# ev_emulator.net
KiCad netlist of a schematic drawn in EAGLE
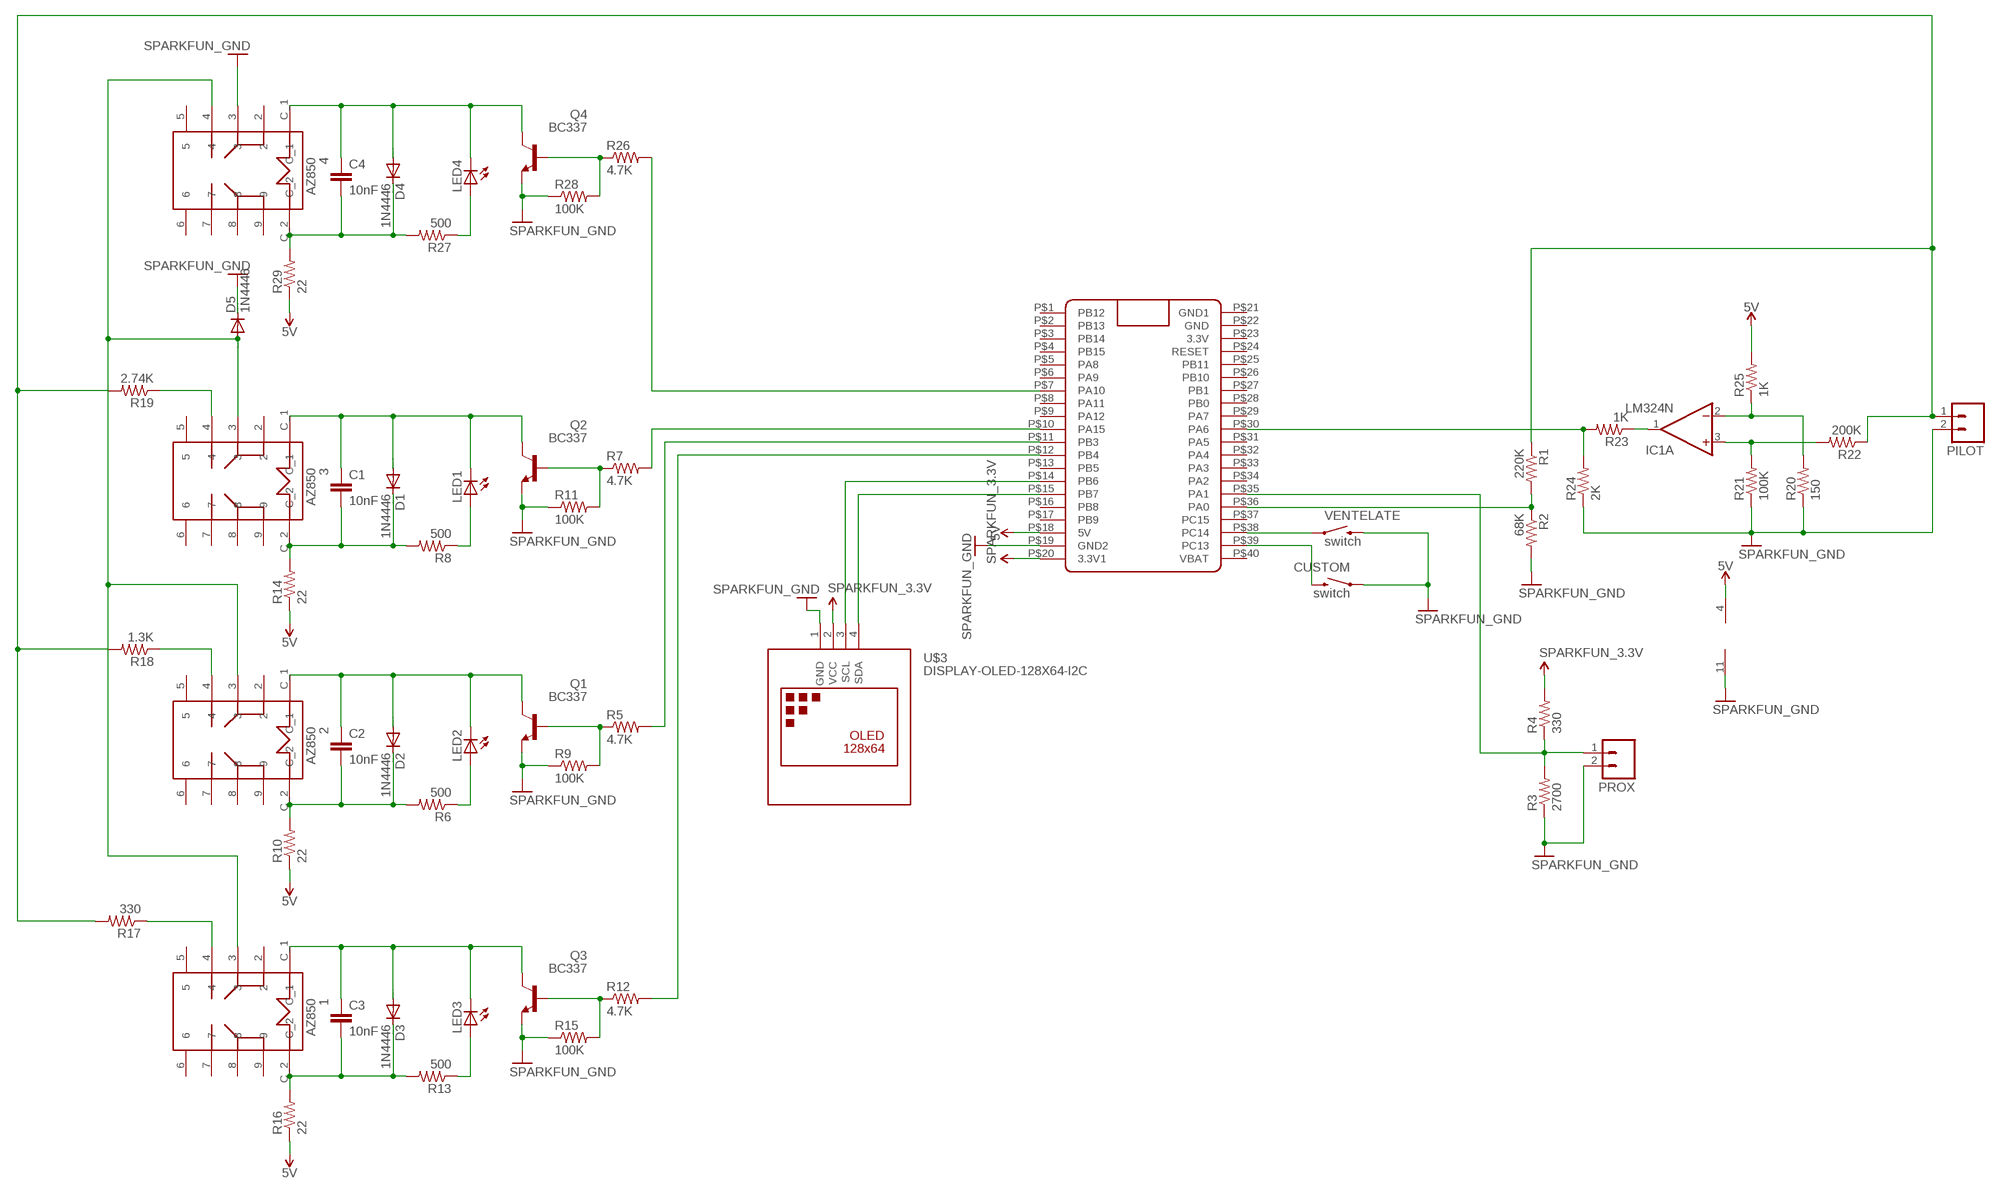
[diagram p0: schematic, sheet 1]

(export (version "E")
  (design (tool "Eeschema 10.0.6"))
  (components
    (comp (ref "1")
      (value "AZ850")
      (footprint "eagle-import:AZ850")
      (libsource (lib "eagle-import") (part "AZ850"))
    )
    (comp (ref "2")
      (value "AZ850")
      (footprint "eagle-import:AZ850")
      (libsource (lib "eagle-import") (part "AZ850"))
    )
    (comp (ref "3")
      (value "AZ850")
      (footprint "eagle-import:AZ850")
      (libsource (lib "eagle-import") (part "AZ850"))
    )
    (comp (ref "4")
      (value "AZ850")
      (footprint "eagle-import:AZ850")
      (libsource (lib "eagle-import") (part "AZ850"))
    )
    (comp (ref "C1")
      (value "10nF")
      (footprint "eagle-import:C2.5-3")
      (libsource (lib "eagle-import") (part "C2,5-3"))
    )
    (comp (ref "C2")
      (value "10nF")
      (footprint "eagle-import:C2.5-3")
      (libsource (lib "eagle-import") (part "C2,5-3"))
    )
    (comp (ref "C3")
      (value "10nF")
      (footprint "eagle-import:C2.5-3")
      (libsource (lib "eagle-import") (part "C2,5-3"))
    )
    (comp (ref "C4")
      (value "10nF")
      (footprint "eagle-import:C2.5-3")
      (libsource (lib "eagle-import") (part "C2,5-3"))
    )
    (comp (ref "CUSTOM")
      (value "switch")
      (footprint "eagle-import:SPARKFUN-ELECTROMECHANICAL_TACTILE-PTH")
      (libsource (lib "eagle-import") (part "SPARKFUN-ELECTROMECHANICAL_SWITCH-MOMENTARY-2PTH"))
    )
    (comp (ref "D1")
      (value "1N4446")
      (footprint "eagle-import:DO35-10")
      (libsource (lib "eagle-import") (part "1N4446"))
    )
    (comp (ref "D2")
      (value "1N4446")
      (footprint "eagle-import:DO35-10")
      (libsource (lib "eagle-import") (part "1N4446"))
    )
    (comp (ref "D3")
      (value "1N4446")
      (footprint "eagle-import:DO35-10")
      (libsource (lib "eagle-import") (part "1N4446"))
    )
    (comp (ref "D4")
      (value "1N4446")
      (footprint "eagle-import:DO35-10")
      (libsource (lib "eagle-import") (part "1N4446"))
    )
    (comp (ref "D5")
      (value "1N4446")
      (footprint "eagle-import:DO35-10")
      (libsource (lib "eagle-import") (part "1N4446"))
    )
    (comp (ref "IC1")
      (value "LM324N")
      (footprint "eagle-import:DIL14")
      (libsource (lib "eagle-import") (part "LM324N"))
    )
    (comp (ref "LED1")
      (value "SPARKFUN_LED-3MM-NO_SILK")
      (footprint "eagle-import:SPARKFUN_LED3MM-NS")
      (libsource (lib "eagle-import") (part "SPARKFUN_LED-3MM-NO_SILK"))
    )
    (comp (ref "LED2")
      (value "SPARKFUN_LED-3MM-NO_SILK")
      (footprint "eagle-import:SPARKFUN_LED3MM-NS")
      (libsource (lib "eagle-import") (part "SPARKFUN_LED-3MM-NO_SILK"))
    )
    (comp (ref "LED3")
      (value "SPARKFUN_LED-3MM-NO_SILK")
      (footprint "eagle-import:SPARKFUN_LED3MM-NS")
      (libsource (lib "eagle-import") (part "SPARKFUN_LED-3MM-NO_SILK"))
    )
    (comp (ref "LED4")
      (value "SPARKFUN_LED-3MM-NO_SILK")
      (footprint "eagle-import:SPARKFUN_LED3MM-NS")
      (libsource (lib "eagle-import") (part "SPARKFUN_LED-3MM-NO_SILK"))
    )
    (comp (ref "PILOT")
      (value "SPARKFUN_M02POLAR")
      (footprint "eagle-import:SPARKFUN_MOLEX-1X2")
      (libsource (lib "eagle-import") (part "SPARKFUN_M02POLAR"))
    )
    (comp (ref "PROX")
      (value "SPARKFUN_M02POLAR")
      (footprint "eagle-import:SPARKFUN_MOLEX-1X2")
      (libsource (lib "eagle-import") (part "SPARKFUN_M02POLAR"))
    )
    (comp (ref "Q1")
      (value "BC337")
      (footprint "eagle-import:TO92")
      (libsource (lib "eagle-import") (part "BC337"))
    )
    (comp (ref "Q2")
      (value "BC337")
      (footprint "eagle-import:TO92")
      (libsource (lib "eagle-import") (part "BC337"))
    )
    (comp (ref "Q3")
      (value "BC337")
      (footprint "eagle-import:TO92")
      (libsource (lib "eagle-import") (part "BC337"))
    )
    (comp (ref "Q4")
      (value "BC337")
      (footprint "eagle-import:TO92")
      (libsource (lib "eagle-import") (part "BC337"))
    )
    (comp (ref "R1")
      (value "220K")
      (footprint "eagle-import:SPARKFUN_AXIAL-0.3")
      (libsource (lib "eagle-import") (part "SPARKFUN_RESISTORAXIAL-0.3"))
    )
    (comp (ref "R2")
      (value "68K")
      (footprint "eagle-import:SPARKFUN_AXIAL-0.3")
      (libsource (lib "eagle-import") (part "SPARKFUN_RESISTORAXIAL-0.3"))
    )
    (comp (ref "R3")
      (value "2700")
      (footprint "eagle-import:SPARKFUN_AXIAL-0.3")
      (libsource (lib "eagle-import") (part "SPARKFUN_RESISTORAXIAL-0.3"))
    )
    (comp (ref "R4")
      (value "330")
      (footprint "eagle-import:SPARKFUN_AXIAL-0.3")
      (libsource (lib "eagle-import") (part "SPARKFUN_RESISTORAXIAL-0.3"))
    )
    (comp (ref "R5")
      (value "4.7K")
      (footprint "eagle-import:SPARKFUN_AXIAL-0.3")
      (libsource (lib "eagle-import") (part "SPARKFUN_RESISTORAXIAL-0.3"))
    )
    (comp (ref "R6")
      (value "500")
      (footprint "eagle-import:SPARKFUN_AXIAL-0.3")
      (libsource (lib "eagle-import") (part "SPARKFUN_RESISTORAXIAL-0.3"))
    )
    (comp (ref "R7")
      (value "4.7K")
      (footprint "eagle-import:SPARKFUN_AXIAL-0.3")
      (libsource (lib "eagle-import") (part "SPARKFUN_RESISTORAXIAL-0.3"))
    )
    (comp (ref "R8")
      (value "500")
      (footprint "eagle-import:SPARKFUN_AXIAL-0.3")
      (libsource (lib "eagle-import") (part "SPARKFUN_RESISTORAXIAL-0.3"))
    )
    (comp (ref "R9")
      (value "100K")
      (footprint "eagle-import:SPARKFUN_AXIAL-0.3")
      (libsource (lib "eagle-import") (part "SPARKFUN_RESISTORAXIAL-0.3"))
    )
    (comp (ref "R10")
      (value "22")
      (footprint "eagle-import:SPARKFUN_AXIAL-0.3")
      (libsource (lib "eagle-import") (part "SPARKFUN_RESISTORAXIAL-0.3"))
    )
    (comp (ref "R11")
      (value "100K")
      (footprint "eagle-import:SPARKFUN_AXIAL-0.3")
      (libsource (lib "eagle-import") (part "SPARKFUN_RESISTORAXIAL-0.3"))
    )
    (comp (ref "R12")
      (value "4.7K")
      (footprint "eagle-import:SPARKFUN_AXIAL-0.3")
      (libsource (lib "eagle-import") (part "SPARKFUN_RESISTORAXIAL-0.3"))
    )
    (comp (ref "R13")
      (value "500")
      (footprint "eagle-import:SPARKFUN_AXIAL-0.3")
      (libsource (lib "eagle-import") (part "SPARKFUN_RESISTORAXIAL-0.3"))
    )
    (comp (ref "R14")
      (value "22")
      (footprint "eagle-import:SPARKFUN_AXIAL-0.3")
      (libsource (lib "eagle-import") (part "SPARKFUN_RESISTORAXIAL-0.3"))
    )
    (comp (ref "R15")
      (value "100K")
      (footprint "eagle-import:SPARKFUN_AXIAL-0.3")
      (libsource (lib "eagle-import") (part "SPARKFUN_RESISTORAXIAL-0.3"))
    )
    (comp (ref "R16")
      (value "22")
      (footprint "eagle-import:SPARKFUN_AXIAL-0.3")
      (libsource (lib "eagle-import") (part "SPARKFUN_RESISTORAXIAL-0.3"))
    )
    (comp (ref "R17")
      (value "330")
      (footprint "eagle-import:SPARKFUN_AXIAL-0.3")
      (libsource (lib "eagle-import") (part "SPARKFUN_RESISTORAXIAL-0.3"))
    )
    (comp (ref "R18")
      (value "1.3K")
      (footprint "eagle-import:SPARKFUN_AXIAL-0.3")
      (libsource (lib "eagle-import") (part "SPARKFUN_RESISTORAXIAL-0.3"))
    )
    (comp (ref "R19")
      (value "2.74K")
      (footprint "eagle-import:SPARKFUN_AXIAL-0.3")
      (libsource (lib "eagle-import") (part "SPARKFUN_RESISTORAXIAL-0.3"))
    )
    (comp (ref "R20")
      (value "150")
      (footprint "eagle-import:SPARKFUN_AXIAL-0.3")
      (libsource (lib "eagle-import") (part "SPARKFUN_RESISTORAXIAL-0.3"))
    )
    (comp (ref "R21")
      (value "100K")
      (footprint "eagle-import:SPARKFUN_AXIAL-0.3")
      (libsource (lib "eagle-import") (part "SPARKFUN_RESISTORAXIAL-0.3"))
    )
    (comp (ref "R22")
      (value "200K")
      (footprint "eagle-import:SPARKFUN_AXIAL-0.3")
      (libsource (lib "eagle-import") (part "SPARKFUN_RESISTORAXIAL-0.3"))
    )
    (comp (ref "R23")
      (value "1K")
      (footprint "eagle-import:SPARKFUN_AXIAL-0.3")
      (libsource (lib "eagle-import") (part "SPARKFUN_RESISTORAXIAL-0.3"))
    )
    (comp (ref "R24")
      (value "2K")
      (footprint "eagle-import:SPARKFUN_AXIAL-0.3")
      (libsource (lib "eagle-import") (part "SPARKFUN_RESISTORAXIAL-0.3"))
    )
    (comp (ref "R25")
      (value "1K")
      (footprint "eagle-import:SPARKFUN_AXIAL-0.3")
      (libsource (lib "eagle-import") (part "SPARKFUN_RESISTORAXIAL-0.3"))
    )
    (comp (ref "R26")
      (value "4.7K")
      (footprint "eagle-import:SPARKFUN_AXIAL-0.3")
      (libsource (lib "eagle-import") (part "SPARKFUN_RESISTORAXIAL-0.3"))
    )
    (comp (ref "R27")
      (value "500")
      (footprint "eagle-import:SPARKFUN_AXIAL-0.3")
      (libsource (lib "eagle-import") (part "SPARKFUN_RESISTORAXIAL-0.3"))
    )
    (comp (ref "R28")
      (value "100K")
      (footprint "eagle-import:SPARKFUN_AXIAL-0.3")
      (libsource (lib "eagle-import") (part "SPARKFUN_RESISTORAXIAL-0.3"))
    )
    (comp (ref "R29")
      (value "22")
      (footprint "eagle-import:SPARKFUN_AXIAL-0.3")
      (libsource (lib "eagle-import") (part "SPARKFUN_RESISTORAXIAL-0.3"))
    )
    (comp (ref "U$1")
      (value "BLUE_PILL")
      (footprint "eagle-import:BLUE_PILL")
      (libsource (lib "eagle-import") (part "BLUE_PILL"))
    )
    (comp (ref "U$3")
      (value "DISPLAY-OLED-128X64-I2C")
      (footprint "eagle-import:DISPLAY-OLED-128X64-I2C")
      (libsource (lib "eagle-import") (part "DISPLAY-OLED-128X64-I2C"))
    )
    (comp (ref "VENTELATE")
      (value "switch")
      (footprint "eagle-import:SPARKFUN-ELECTROMECHANICAL_TACTILE-PTH")
      (libsource (lib "eagle-import") (part "SPARKFUN-ELECTROMECHANICAL_SWITCH-MOMENTARY-2PTH"))
    )
  )
  (nets
    (net (code "1") (name "/GND1") (class "Default")
      (node (ref "U$1") (pin "P$21") (pinfunction "GND1_P$21") (pintype "power_in"))
    )
    (net (code "2") (name "5V") (class "Default")
      (node (ref "IC1") (pin "4") (pinfunction "V+_4") (pintype "power_in"))
      (node (ref "R10") (pin "P$1") (pinfunction "1_P$1") (pintype "passive"))
      (node (ref "R14") (pin "P$1") (pinfunction "1_P$1") (pintype "passive"))
      (node (ref "R16") (pin "P$1") (pinfunction "1_P$1") (pintype "passive"))
      (node (ref "R25") (pin "P$2") (pinfunction "2_P$2") (pintype "passive"))
      (node (ref "R29") (pin "P$1") (pinfunction "1_P$1") (pintype "passive"))
      (node (ref "U$1") (pin "P$18") (pinfunction "5V_P$18") (pintype "bidirectional"))
    )
    (net (code "3") (name "Net-(1-Pad3)") (class "Default")
      (node (ref "1") (pin "3") (pinfunction "3_3") (pintype "bidirectional"))
      (node (ref "2") (pin "3") (pinfunction "3_3") (pintype "bidirectional"))
      (node (ref "3") (pin "3") (pinfunction "3_3") (pintype "bidirectional"))
      (node (ref "4") (pin "4") (pinfunction "4_4") (pintype "bidirectional"))
      (node (ref "D5") (pin "A") (pinfunction "A_A") (pintype "passive"))
    )
    (net (code "4") (name "Net-(1-С_1)") (class "Default")
      (node (ref "1") (pin "C_1") (pinfunction "С_1_C_1") (pintype "power_in"))
      (node (ref "C3") (pin "1") (pinfunction "1_1") (pintype "passive"))
      (node (ref "D3") (pin "A") (pinfunction "A_A") (pintype "passive"))
      (node (ref "LED3") (pin "K") (pinfunction "C_K") (pintype "passive"))
      (node (ref "Q3") (pin "3") (pinfunction "C_3") (pintype "passive"))
    )
    (net (code "5") (name "Net-(1-С_2)") (class "Default")
      (node (ref "1") (pin "C_2") (pinfunction "С_2_C_2") (pintype "power_in"))
      (node (ref "C3") (pin "2") (pinfunction "2_2") (pintype "passive"))
      (node (ref "D3") (pin "C") (pinfunction "C_C") (pintype "passive"))
      (node (ref "R13") (pin "P$2") (pinfunction "2_P$2") (pintype "passive"))
      (node (ref "R16") (pin "P$2") (pinfunction "2_P$2") (pintype "passive"))
    )
    (net (code "6") (name "Net-(2-С_1)") (class "Default")
      (node (ref "2") (pin "C_1") (pinfunction "С_1_C_1") (pintype "power_in"))
      (node (ref "C2") (pin "1") (pinfunction "1_1") (pintype "passive"))
      (node (ref "D2") (pin "A") (pinfunction "A_A") (pintype "passive"))
      (node (ref "LED2") (pin "K") (pinfunction "C_K") (pintype "passive"))
      (node (ref "Q1") (pin "3") (pinfunction "C_3") (pintype "passive"))
    )
    (net (code "7") (name "Net-(2-С_2)") (class "Default")
      (node (ref "2") (pin "C_2") (pinfunction "С_2_C_2") (pintype "power_in"))
      (node (ref "C2") (pin "2") (pinfunction "2_2") (pintype "passive"))
      (node (ref "D2") (pin "C") (pinfunction "C_C") (pintype "passive"))
      (node (ref "R10") (pin "P$2") (pinfunction "2_P$2") (pintype "passive"))
      (node (ref "R6") (pin "P$2") (pinfunction "2_P$2") (pintype "passive"))
    )
    (net (code "8") (name "Net-(3-С_1)") (class "Default")
      (node (ref "3") (pin "C_1") (pinfunction "С_1_C_1") (pintype "power_in"))
      (node (ref "C1") (pin "1") (pinfunction "1_1") (pintype "passive"))
      (node (ref "D1") (pin "A") (pinfunction "A_A") (pintype "passive"))
      (node (ref "LED1") (pin "K") (pinfunction "C_K") (pintype "passive"))
      (node (ref "Q2") (pin "3") (pinfunction "C_3") (pintype "passive"))
    )
    (net (code "9") (name "Net-(3-С_2)") (class "Default")
      (node (ref "3") (pin "C_2") (pinfunction "С_2_C_2") (pintype "power_in"))
      (node (ref "C1") (pin "2") (pinfunction "2_2") (pintype "passive"))
      (node (ref "D1") (pin "C") (pinfunction "C_C") (pintype "passive"))
      (node (ref "R14") (pin "P$2") (pinfunction "2_P$2") (pintype "passive"))
      (node (ref "R8") (pin "P$2") (pinfunction "2_P$2") (pintype "passive"))
    )
    (net (code "10") (name "Net-(4-С_1)") (class "Default")
      (node (ref "4") (pin "C_1") (pinfunction "С_1_C_1") (pintype "power_in"))
      (node (ref "C4") (pin "1") (pinfunction "1_1") (pintype "passive"))
      (node (ref "D4") (pin "A") (pinfunction "A_A") (pintype "passive"))
      (node (ref "LED4") (pin "K") (pinfunction "C_K") (pintype "passive"))
      (node (ref "Q4") (pin "3") (pinfunction "C_3") (pintype "passive"))
    )
    (net (code "11") (name "Net-(4-С_2)") (class "Default")
      (node (ref "4") (pin "C_2") (pinfunction "С_2_C_2") (pintype "power_in"))
      (node (ref "C4") (pin "2") (pinfunction "2_2") (pintype "passive"))
      (node (ref "D4") (pin "C") (pinfunction "C_C") (pintype "passive"))
      (node (ref "R27") (pin "P$2") (pinfunction "2_P$2") (pintype "passive"))
      (node (ref "R29") (pin "P$2") (pinfunction "2_P$2") (pintype "passive"))
    )
    (net (code "12") (name "Net-(CUSTOM-2)") (class "Default")
      (node (ref "CUSTOM") (pin "3") (pinfunction "2_3") (pintype "passive"))
      (node (ref "U$1") (pin "P$39") (pinfunction "PC13_P$39") (pintype "bidirectional"))
    )
    (net (code "13") (name "Net-(IC1A-+IN)") (class "Default")
      (node (ref "IC1") (pin "3") (pinfunction "+IN_3") (pintype "input"))
      (node (ref "R21") (pin "P$2") (pinfunction "2_P$2") (pintype "passive"))
      (node (ref "R22") (pin "P$2") (pinfunction "2_P$2") (pintype "passive"))
    )
    (net (code "14") (name "Net-(IC1A--IN)") (class "Default")
      (node (ref "IC1") (pin "2") (pinfunction "-IN_2") (pintype "input"))
      (node (ref "R20") (pin "P$2") (pinfunction "2_P$2") (pintype "passive"))
      (node (ref "R25") (pin "P$1") (pinfunction "1_P$1") (pintype "passive"))
    )
    (net (code "15") (name "Net-(IC1A-OUT)") (class "Default")
      (node (ref "IC1") (pin "1") (pinfunction "OUT_1") (pintype "output"))
      (node (ref "R23") (pin "P$1") (pinfunction "1_P$1") (pintype "passive"))
    )
    (net (code "16") (name "Net-(Q1-B)") (class "Default")
      (node (ref "Q1") (pin "2") (pinfunction "B_2") (pintype "passive"))
      (node (ref "R5") (pin "P$1") (pinfunction "1_P$1") (pintype "passive"))
      (node (ref "R9") (pin "P$2") (pinfunction "2_P$2") (pintype "passive"))
    )
    (net (code "17") (name "Net-(Q2-B)") (class "Default")
      (node (ref "Q2") (pin "2") (pinfunction "B_2") (pintype "passive"))
      (node (ref "R11") (pin "P$2") (pinfunction "2_P$2") (pintype "passive"))
      (node (ref "R7") (pin "P$1") (pinfunction "1_P$1") (pintype "passive"))
    )
    (net (code "18") (name "Net-(Q3-B)") (class "Default")
      (node (ref "Q3") (pin "2") (pinfunction "B_2") (pintype "passive"))
      (node (ref "R12") (pin "P$1") (pinfunction "1_P$1") (pintype "passive"))
      (node (ref "R15") (pin "P$2") (pinfunction "2_P$2") (pintype "passive"))
    )
    (net (code "19") (name "Net-(Q4-B)") (class "Default")
      (node (ref "Q4") (pin "2") (pinfunction "B_2") (pintype "passive"))
      (node (ref "R26") (pin "P$1") (pinfunction "1_P$1") (pintype "passive"))
      (node (ref "R28") (pin "P$2") (pinfunction "2_P$2") (pintype "passive"))
    )
    (net (code "20") (name "Net-(R1-1)") (class "Default")
      (node (ref "PILOT") (pin "1") (pinfunction "1_1") (pintype "passive"))
      (node (ref "R1") (pin "P$1") (pinfunction "1_P$1") (pintype "passive"))
      (node (ref "R17") (pin "P$2") (pinfunction "2_P$2") (pintype "passive"))
      (node (ref "R18") (pin "P$2") (pinfunction "2_P$2") (pintype "passive"))
      (node (ref "R19") (pin "P$2") (pinfunction "2_P$2") (pintype "passive"))
      (node (ref "R22") (pin "P$1") (pinfunction "1_P$1") (pintype "passive"))
    )
    (net (code "21") (name "Net-(R1-2)") (class "Default")
      (node (ref "R1") (pin "P$2") (pinfunction "2_P$2") (pintype "passive"))
      (node (ref "R2") (pin "P$1") (pinfunction "1_P$1") (pintype "passive"))
      (node (ref "U$1") (pin "P$36") (pinfunction "PA0_P$36") (pintype "bidirectional"))
    )
    (net (code "22") (name "Net-(R3-2)") (class "Default")
      (node (ref "PROX") (pin "1") (pinfunction "1_1") (pintype "passive"))
      (node (ref "R3") (pin "P$2") (pinfunction "2_P$2") (pintype "passive"))
      (node (ref "R4") (pin "P$1") (pinfunction "1_P$1") (pintype "passive"))
      (node (ref "U$1") (pin "P$35") (pinfunction "PA1_P$35") (pintype "bidirectional"))
    )
    (net (code "23") (name "Net-(R5-2)") (class "Default")
      (node (ref "R5") (pin "P$2") (pinfunction "2_P$2") (pintype "passive"))
      (node (ref "U$1") (pin "P$11") (pinfunction "PB3_P$11") (pintype "bidirectional"))
    )
    (net (code "24") (name "Net-(R6-1)") (class "Default")
      (node (ref "LED2") (pin "A") (pinfunction "A_A") (pintype "passive"))
      (node (ref "R6") (pin "P$1") (pinfunction "1_P$1") (pintype "passive"))
    )
    (net (code "25") (name "Net-(R7-2)") (class "Default")
      (node (ref "R7") (pin "P$2") (pinfunction "2_P$2") (pintype "passive"))
      (node (ref "U$1") (pin "P$10") (pinfunction "PA15_P$10") (pintype "bidirectional"))
    )
    (net (code "26") (name "Net-(R8-1)") (class "Default")
      (node (ref "LED1") (pin "A") (pinfunction "A_A") (pintype "passive"))
      (node (ref "R8") (pin "P$1") (pinfunction "1_P$1") (pintype "passive"))
    )
    (net (code "27") (name "Net-(R12-2)") (class "Default")
      (node (ref "R12") (pin "P$2") (pinfunction "2_P$2") (pintype "passive"))
      (node (ref "U$1") (pin "P$12") (pinfunction "PB4_P$12") (pintype "bidirectional"))
    )
    (net (code "28") (name "Net-(R13-1)") (class "Default")
      (node (ref "LED3") (pin "A") (pinfunction "A_A") (pintype "passive"))
      (node (ref "R13") (pin "P$1") (pinfunction "1_P$1") (pintype "passive"))
    )
    (net (code "29") (name "Net-(R17-1)") (class "Default")
      (node (ref "1") (pin "4") (pinfunction "4_4") (pintype "bidirectional"))
      (node (ref "R17") (pin "P$1") (pinfunction "1_P$1") (pintype "passive"))
    )
    (net (code "30") (name "Net-(R18-1)") (class "Default")
      (node (ref "2") (pin "4") (pinfunction "4_4") (pintype "bidirectional"))
      (node (ref "R18") (pin "P$1") (pinfunction "1_P$1") (pintype "passive"))
    )
    (net (code "31") (name "Net-(R19-1)") (class "Default")
      (node (ref "3") (pin "4") (pinfunction "4_4") (pintype "bidirectional"))
      (node (ref "R19") (pin "P$1") (pinfunction "1_P$1") (pintype "passive"))
    )
    (net (code "32") (name "Net-(R23-2)") (class "Default")
      (node (ref "R23") (pin "P$2") (pinfunction "2_P$2") (pintype "passive"))
      (node (ref "R24") (pin "P$2") (pinfunction "2_P$2") (pintype "passive"))
      (node (ref "U$1") (pin "P$30") (pinfunction "PA6_P$30") (pintype "bidirectional"))
    )
    (net (code "33") (name "Net-(R26-2)") (class "Default")
      (node (ref "R26") (pin "P$2") (pinfunction "2_P$2") (pintype "passive"))
      (node (ref "U$1") (pin "P$7") (pinfunction "PA10_P$7") (pintype "bidirectional"))
    )
    (net (code "34") (name "Net-(R27-1)") (class "Default")
      (node (ref "LED4") (pin "A") (pinfunction "A_A") (pintype "passive"))
      (node (ref "R27") (pin "P$1") (pinfunction "1_P$1") (pintype "passive"))
    )
    (net (code "35") (name "Net-(U$1-PB6)") (class "Default")
      (node (ref "U$1") (pin "P$14") (pinfunction "PB6_P$14") (pintype "bidirectional"))
      (node (ref "U$3") (pin "3") (pinfunction "SCL_3") (pintype "bidirectional"))
    )
    (net (code "36") (name "Net-(U$1-PB7)") (class "Default")
      (node (ref "U$1") (pin "P$15") (pinfunction "PB7_P$15") (pintype "bidirectional"))
      (node (ref "U$3") (pin "4") (pinfunction "SDA_4") (pintype "bidirectional"))
    )
    (net (code "37") (name "Net-(U$1-PC14)") (class "Default")
      (node (ref "U$1") (pin "P$38") (pinfunction "PC14_P$38") (pintype "bidirectional"))
      (node (ref "VENTELATE") (pin "1") (pinfunction "1_1") (pintype "passive"))
    )
    (net (code "38") (name "SPARKFUN_3.3V") (class "Default")
      (node (ref "R4") (pin "P$2") (pinfunction "2_P$2") (pintype "passive"))
      (node (ref "U$1") (pin "P$20") (pinfunction "3.3V1_P$20") (pintype "bidirectional"))
      (node (ref "U$3") (pin "2") (pinfunction "VCC_2") (pintype "power_in"))
    )
    (net (code "39") (name "SPARKFUN_GND") (class "Default")
      (node (ref "4") (pin "3") (pinfunction "3_3") (pintype "bidirectional"))
      (node (ref "CUSTOM") (pin "1") (pinfunction "1_1") (pintype "passive"))
      (node (ref "D5") (pin "C") (pinfunction "C_C") (pintype "passive"))
      (node (ref "IC1") (pin "11") (pinfunction "V-_11") (pintype "power_in"))
      (node (ref "PILOT") (pin "2") (pinfunction "2_2") (pintype "passive"))
      (node (ref "PROX") (pin "2") (pinfunction "2_2") (pintype "passive"))
      (node (ref "Q1") (pin "1") (pinfunction "E_1") (pintype "passive"))
      (node (ref "Q2") (pin "1") (pinfunction "E_1") (pintype "passive"))
      (node (ref "Q3") (pin "1") (pinfunction "E_1") (pintype "passive"))
      (node (ref "Q4") (pin "1") (pinfunction "E_1") (pintype "passive"))
      (node (ref "R11") (pin "P$1") (pinfunction "1_P$1") (pintype "passive"))
      (node (ref "R15") (pin "P$1") (pinfunction "1_P$1") (pintype "passive"))
      (node (ref "R2") (pin "P$2") (pinfunction "2_P$2") (pintype "passive"))
      (node (ref "R20") (pin "P$1") (pinfunction "1_P$1") (pintype "passive"))
      (node (ref "R21") (pin "P$1") (pinfunction "1_P$1") (pintype "passive"))
      (node (ref "R24") (pin "P$1") (pinfunction "1_P$1") (pintype "passive"))
      (node (ref "R28") (pin "P$1") (pinfunction "1_P$1") (pintype "passive"))
      (node (ref "R3") (pin "P$1") (pinfunction "1_P$1") (pintype "passive"))
      (node (ref "R9") (pin "P$1") (pinfunction "1_P$1") (pintype "passive"))
      (node (ref "U$1") (pin "P$19") (pinfunction "GND2_P$19") (pintype "bidirectional"))
      (node (ref "U$3") (pin "1") (pinfunction "GND_1") (pintype "power_in"))
      (node (ref "VENTELATE") (pin "3") (pinfunction "2_3") (pintype "passive"))
    )
    (net (code "40") (name "unconnected-(1-Pad2)") (class "Default")
      (node (ref "1") (pin "2") (pinfunction "2_2") (pintype "bidirectional"))
    )
    (net (code "41") (name "unconnected-(1-Pad5)") (class "Default")
      (node (ref "1") (pin "5") (pinfunction "5_5") (pintype "bidirectional"))
    )
    (net (code "42") (name "unconnected-(1-Pad6)") (class "Default")
      (node (ref "1") (pin "6") (pinfunction "6_6") (pintype "bidirectional"))
    )
    (net (code "43") (name "unconnected-(1-Pad7)") (class "Default")
      (node (ref "1") (pin "7") (pinfunction "7_7") (pintype "bidirectional"))
    )
    (net (code "44") (name "unconnected-(1-Pad8)") (class "Default")
      (node (ref "1") (pin "8") (pinfunction "8_8") (pintype "bidirectional"))
    )
    (net (code "45") (name "unconnected-(1-Pad9)") (class "Default")
      (node (ref "1") (pin "9") (pinfunction "9_9") (pintype "bidirectional"))
    )
    (net (code "46") (name "unconnected-(2-Pad2)") (class "Default")
      (node (ref "2") (pin "2") (pinfunction "2_2") (pintype "bidirectional"))
    )
    (net (code "47") (name "unconnected-(2-Pad5)") (class "Default")
      (node (ref "2") (pin "5") (pinfunction "5_5") (pintype "bidirectional"))
    )
    (net (code "48") (name "unconnected-(2-Pad6)") (class "Default")
      (node (ref "2") (pin "6") (pinfunction "6_6") (pintype "bidirectional"))
    )
    (net (code "49") (name "unconnected-(2-Pad7)") (class "Default")
      (node (ref "2") (pin "7") (pinfunction "7_7") (pintype "bidirectional"))
    )
    (net (code "50") (name "unconnected-(2-Pad8)") (class "Default")
      (node (ref "2") (pin "8") (pinfunction "8_8") (pintype "bidirectional"))
    )
    (net (code "51") (name "unconnected-(2-Pad9)") (class "Default")
      (node (ref "2") (pin "9") (pinfunction "9_9") (pintype "bidirectional"))
    )
    (net (code "52") (name "unconnected-(3-Pad2)") (class "Default")
      (node (ref "3") (pin "2") (pinfunction "2_2") (pintype "bidirectional"))
    )
    (net (code "53") (name "unconnected-(3-Pad5)") (class "Default")
      (node (ref "3") (pin "5") (pinfunction "5_5") (pintype "bidirectional"))
    )
    (net (code "54") (name "unconnected-(3-Pad6)") (class "Default")
      (node (ref "3") (pin "6") (pinfunction "6_6") (pintype "bidirectional"))
    )
    (net (code "55") (name "unconnected-(3-Pad7)") (class "Default")
      (node (ref "3") (pin "7") (pinfunction "7_7") (pintype "bidirectional"))
    )
    (net (code "56") (name "unconnected-(3-Pad8)") (class "Default")
      (node (ref "3") (pin "8") (pinfunction "8_8") (pintype "bidirectional"))
    )
    (net (code "57") (name "unconnected-(3-Pad9)") (class "Default")
      (node (ref "3") (pin "9") (pinfunction "9_9") (pintype "bidirectional"))
    )
    (net (code "58") (name "unconnected-(4-Pad2)") (class "Default")
      (node (ref "4") (pin "2") (pinfunction "2_2") (pintype "bidirectional"))
    )
    (net (code "59") (name "unconnected-(4-Pad5)") (class "Default")
      (node (ref "4") (pin "5") (pinfunction "5_5") (pintype "bidirectional"))
    )
    (net (code "60") (name "unconnected-(4-Pad6)") (class "Default")
      (node (ref "4") (pin "6") (pinfunction "6_6") (pintype "bidirectional"))
    )
    (net (code "61") (name "unconnected-(4-Pad7)") (class "Default")
      (node (ref "4") (pin "7") (pinfunction "7_7") (pintype "bidirectional"))
    )
    (net (code "62") (name "unconnected-(4-Pad8)") (class "Default")
      (node (ref "4") (pin "8") (pinfunction "8_8") (pintype "bidirectional"))
    )
    (net (code "63") (name "unconnected-(4-Pad9)") (class "Default")
      (node (ref "4") (pin "9") (pinfunction "9_9") (pintype "bidirectional"))
    )
    (net (code "64") (name "unconnected-(U$1-3.3V-PadP$23)") (class "Default")
      (node (ref "U$1") (pin "P$23") (pinfunction "3.3V_P$23") (pintype "bidirectional"))
    )
    (net (code "65") (name "unconnected-(U$1-GND-PadP$22)") (class "Default")
      (node (ref "U$1") (pin "P$22") (pinfunction "GND_P$22") (pintype "bidirectional"))
    )
    (net (code "66") (name "unconnected-(U$1-PA2-PadP$34)") (class "Default")
      (node (ref "U$1") (pin "P$34") (pinfunction "PA2_P$34") (pintype "bidirectional"))
    )
    (net (code "67") (name "unconnected-(U$1-PA3-PadP$33)") (class "Default")
      (node (ref "U$1") (pin "P$33") (pinfunction "PA3_P$33") (pintype "bidirectional"))
    )
    (net (code "68") (name "unconnected-(U$1-PA4-PadP$32)") (class "Default")
      (node (ref "U$1") (pin "P$32") (pinfunction "PA4_P$32") (pintype "bidirectional"))
    )
    (net (code "69") (name "unconnected-(U$1-PA5-PadP$31)") (class "Default")
      (node (ref "U$1") (pin "P$31") (pinfunction "PA5_P$31") (pintype "bidirectional"))
    )
    (net (code "70") (name "unconnected-(U$1-PA7-PadP$29)") (class "Default")
      (node (ref "U$1") (pin "P$29") (pinfunction "PA7_P$29") (pintype "bidirectional"))
    )
    (net (code "71") (name "unconnected-(U$1-PA8-PadP$5)") (class "Default")
      (node (ref "U$1") (pin "P$5") (pinfunction "PA8_P$5") (pintype "bidirectional"))
    )
    (net (code "72") (name "unconnected-(U$1-PA9-PadP$6)") (class "Default")
      (node (ref "U$1") (pin "P$6") (pinfunction "PA9_P$6") (pintype "bidirectional"))
    )
    (net (code "73") (name "unconnected-(U$1-PA11-PadP$8)") (class "Default")
      (node (ref "U$1") (pin "P$8") (pinfunction "PA11_P$8") (pintype "bidirectional"))
    )
    (net (code "74") (name "unconnected-(U$1-PA12-PadP$9)") (class "Default")
      (node (ref "U$1") (pin "P$9") (pinfunction "PA12_P$9") (pintype "bidirectional"))
    )
    (net (code "75") (name "unconnected-(U$1-PB0-PadP$28)") (class "Default")
      (node (ref "U$1") (pin "P$28") (pinfunction "PB0_P$28") (pintype "bidirectional"))
    )
    (net (code "76") (name "unconnected-(U$1-PB1-PadP$27)") (class "Default")
      (node (ref "U$1") (pin "P$27") (pinfunction "PB1_P$27") (pintype "bidirectional"))
    )
    (net (code "77") (name "unconnected-(U$1-PB5-PadP$13)") (class "Default")
      (node (ref "U$1") (pin "P$13") (pinfunction "PB5_P$13") (pintype "bidirectional"))
    )
    (net (code "78") (name "unconnected-(U$1-PB8-PadP$16)") (class "Default")
      (node (ref "U$1") (pin "P$16") (pinfunction "PB8_P$16") (pintype "bidirectional"))
    )
    (net (code "79") (name "unconnected-(U$1-PB9-PadP$17)") (class "Default")
      (node (ref "U$1") (pin "P$17") (pinfunction "PB9_P$17") (pintype "bidirectional"))
    )
    (net (code "80") (name "unconnected-(U$1-PB10-PadP$26)") (class "Default")
      (node (ref "U$1") (pin "P$26") (pinfunction "PB10_P$26") (pintype "bidirectional"))
    )
    (net (code "81") (name "unconnected-(U$1-PB11-PadP$25)") (class "Default")
      (node (ref "U$1") (pin "P$25") (pinfunction "PB11_P$25") (pintype "bidirectional"))
    )
    (net (code "82") (name "unconnected-(U$1-PB12-PadP$1)") (class "Default")
      (node (ref "U$1") (pin "P$1") (pinfunction "PB12_P$1") (pintype "bidirectional"))
    )
    (net (code "83") (name "unconnected-(U$1-PB13-PadP$2)") (class "Default")
      (node (ref "U$1") (pin "P$2") (pinfunction "PB13_P$2") (pintype "bidirectional"))
    )
    (net (code "84") (name "unconnected-(U$1-PB14-PadP$3)") (class "Default")
      (node (ref "U$1") (pin "P$3") (pinfunction "PB14_P$3") (pintype "bidirectional"))
    )
    (net (code "85") (name "unconnected-(U$1-PB15-PadP$4)") (class "Default")
      (node (ref "U$1") (pin "P$4") (pinfunction "PB15_P$4") (pintype "bidirectional"))
    )
    (net (code "86") (name "unconnected-(U$1-PC15-PadP$37)") (class "Default")
      (node (ref "U$1") (pin "P$37") (pinfunction "PC15_P$37") (pintype "bidirectional"))
    )
    (net (code "87") (name "unconnected-(U$1-RESET-PadP$24)") (class "Default")
      (node (ref "U$1") (pin "P$24") (pinfunction "RESET_P$24") (pintype "bidirectional"))
    )
    (net (code "88") (name "unconnected-(U$1-VBAT-PadP$40)") (class "Default")
      (node (ref "U$1") (pin "P$40") (pinfunction "VBAT_P$40") (pintype "bidirectional"))
    )
  )
)
